# reTerm-HW-M-IOLINK-HMT.net
KiCad netlist of a schematic drawn in Altium Designer
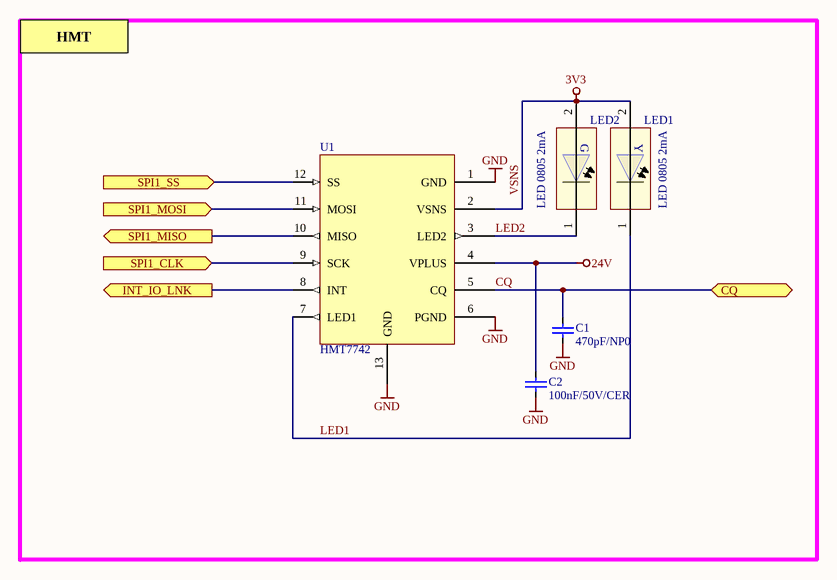
[diagram p0: reTerm-HW-M-IOLINK-HMT.SchDoc]

(export (version "E")
  (design (tool "Eeschema 10.0.6"))
  (components
    (comp (ref "C1")
      (value "470pF/NP0")
      (footprint "C0603")
      (libsource (lib "HE_Lib") (part "CAP_470pF_NP0_"))
    )
    (comp (ref "C2")
      (value "100nF/50V/CER")
      (footprint "C0603")
      (libsource (lib "HE_Lib") (part "CAP_100nF_50V_CER"))
    )
    (comp (ref "LED1")
      (value "LED 0805 2mA")
      (footprint "LED-0805-APT2012")
      (description "LED-APT2012LSYCK/J3-PRV YEL 0805 2mA")
      (libsource (lib "HE_Lib") (part "LED-APT2012LSYCK/J3-PRV"))
    )
    (comp (ref "LED2")
      (value "LED 0805 2mA")
      (footprint "LED-0805-APT2012")
      (description "LED-APT2012LSECK/J3-PRV GREEN 0805 2mA")
      (libsource (lib "HE_Lib") (part "LED-APT2012LSECK/J3-PRV"))
    )
    (comp (ref "U1")
      (value "HMT7742")
      (footprint "DFN 12LD 4x3")
      (description "HMT7742 GENIE IO-Link DEVICE PHY")
      (libsource (lib "HE_Lib") (part "HMT7742"))
    )
  )
  (nets
    (net (code "1") (name "/CQ") (class "Default")
      (node (ref "C1") (pin "1") (pinfunction "1_1") (pintype "passive"))
      (node (ref "U1") (pin "5") (pinfunction "CQ_5") (pintype "passive"))
    )
    (net (code "2") (name "/INT_IO_LNK") (class "Default")
      (node (ref "U1") (pin "8") (pinfunction "INT_8") (pintype "output"))
    )
    (net (code "3") (name "/LED1") (class "Default")
      (node (ref "LED1") (pin "1") (pinfunction "1_1") (pintype "passive"))
      (node (ref "U1") (pin "7") (pinfunction "LED1_7") (pintype "output"))
    )
    (net (code "4") (name "/LED2") (class "Default")
      (node (ref "LED2") (pin "1") (pinfunction "1_1") (pintype "passive"))
      (node (ref "U1") (pin "3") (pinfunction "LED2_3") (pintype "output"))
    )
    (net (code "5") (name "/SPI1_CLK") (class "Default")
      (node (ref "U1") (pin "9") (pinfunction "SCK_9") (pintype "input"))
    )
    (net (code "6") (name "/SPI1_MISO") (class "Default")
      (node (ref "U1") (pin "10") (pinfunction "MISO_10") (pintype "output"))
    )
    (net (code "7") (name "/SPI1_MOSI") (class "Default")
      (node (ref "U1") (pin "11") (pinfunction "MOSI_11") (pintype "input"))
    )
    (net (code "8") (name "/SPI1_SS") (class "Default")
      (node (ref "U1") (pin "12") (pinfunction "SS_12") (pintype "input"))
    )
    (net (code "9") (name "3V3") (class "Default")
      (node (ref "LED1") (pin "2") (pinfunction "2_2") (pintype "passive"))
      (node (ref "LED2") (pin "2") (pinfunction "2_2") (pintype "passive"))
      (node (ref "U1") (pin "2") (pinfunction "VSNS_2") (pintype "passive"))
    )
    (net (code "10") (name "24V") (class "Default")
      (node (ref "C2") (pin "1") (pinfunction "1_1") (pintype "passive"))
      (node (ref "U1") (pin "4") (pinfunction "VPLUS_4") (pintype "power_in"))
    )
    (net (code "11") (name "GND") (class "Default")
      (node (ref "C1") (pin "2") (pinfunction "2_2") (pintype "passive"))
      (node (ref "C2") (pin "2") (pinfunction "2_2") (pintype "passive"))
      (node (ref "U1") (pin "1") (pinfunction "GND_1") (pintype "power_in"))
      (node (ref "U1") (pin "13") (pinfunction "GND_13") (pintype "power_in"))
      (node (ref "U1") (pin "6") (pinfunction "PGND_6") (pintype "power_in"))
    )
  )
)
